# ESP32-WROOM-32.net
KiCad netlist of a schematic drawn in Altium Designer
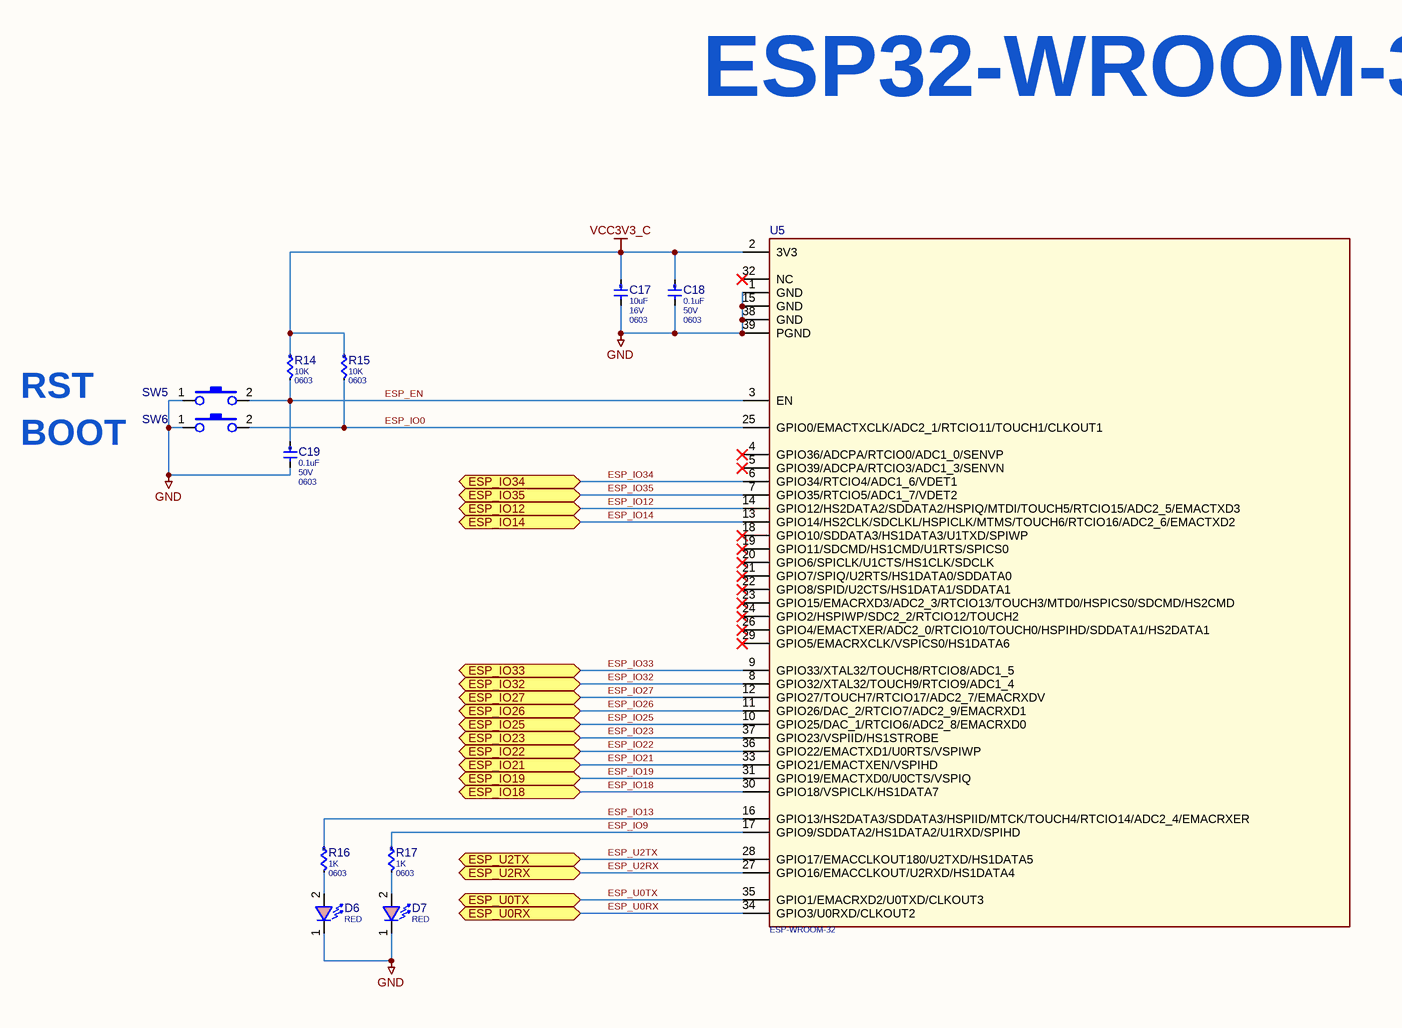
[diagram p0: ESP32-WROOM-32.SchDoc]

(export (version "E")
  (design (tool "Eeschema 10.0.6"))
  (components
    (comp (ref "C17")
      (value "10uF")
      (footprint "C0603")
      (description "CAP CER 10UF 10% 16V X5R 0603 SMD")
      (fields
        (field (name "TOLERANCE") "10%")
        (field (name "VOLTAGE") "16V")
        (field (name "PACK") "0603")
        (field (name "Comment") "10uF 16V 0603")
      )
      (libsource (lib "FENIKAA_LIB") (part "C0603_10uF_16V_10%"))
    )
    (comp (ref "C18")
      (value "0.1uF")
      (footprint "C0603")
      (description "CAP CER 0.1UF 10% 50V X7R 0603 SMD")
      (fields
        (field (name "TOLERANCE") "10%")
        (field (name "VOLTAGE") "50V")
        (field (name "PACK") "0603")
        (field (name "Comment") "0.1uF 50V 0603")
      )
      (libsource (lib "FENIKAA_LIB") (part "C0603_0.1uF_50V_10%"))
    )
    (comp (ref "C19")
      (value "0.1uF")
      (footprint "C0603")
      (description "CAP CER 0.1UF 10% 50V X7R 0603 SMD")
      (fields
        (field (name "TOLERANCE") "10%")
        (field (name "VOLTAGE") "50V")
        (field (name "PACK") "0603")
        (field (name "Comment") "0.1uF 50V 0603")
      )
      (libsource (lib "FENIKAA_LIB") (part "C0603_0.1uF_50V_10%"))
    )
    (comp (ref "D6")
      (value "LH R974-LP-1")
      (footprint "LED0805_RED")
      (description "LED IND RED 1.8V 20mA 0805 SMD")
      (fields (field (name "COLOR") "RED"))
      (libsource (lib "FENIKAA_LIB") (part "LED0805_RED"))
    )
    (comp (ref "D7")
      (value "LH R974-LP-1")
      (footprint "LED0805_RED")
      (description "LED IND RED 1.8V 20mA 0805 SMD")
      (fields (field (name "COLOR") "RED"))
      (libsource (lib "FENIKAA_LIB") (part "LED0805_RED"))
    )
    (comp (ref "R14")
      (value "10K")
      (footprint "R0603")
      (description "RES CHP 10K 1% 1/10W 0603 SMD")
      (fields (field (name "POWER") "1/10W") (field (name "PACK") "0603") (field (name "TOLERANCE") "1%"))
      (libsource (lib "FENIKAA_LIB") (part "R0603_10K_1/10W_1%"))
    )
    (comp (ref "R15")
      (value "10K")
      (footprint "R0603")
      (description "RES CHP 10K 1% 1/10W 0603 SMD")
      (fields (field (name "POWER") "1/10W") (field (name "PACK") "0603") (field (name "TOLERANCE") "1%"))
      (libsource (lib "FENIKAA_LIB") (part "R0603_10K_1/10W_1%"))
    )
    (comp (ref "R16")
      (value "1K")
      (footprint "R0603")
      (description "RES CHP 1K 1% 1/10W 0603 SMD")
      (fields (field (name "POWER") "1/10W") (field (name "PACK") "0603") (field (name "TOLERANCE") "1%"))
      (libsource (lib "FENIKAA_LIB") (part "R0603_1K_1/10W_1%"))
    )
    (comp (ref "R17")
      (value "1K")
      (footprint "R0603")
      (description "RES CHP 1K 1% 1/10W 0603 SMD")
      (fields (field (name "POWER") "1/10W") (field (name "PACK") "0603") (field (name "TOLERANCE") "1%"))
      (libsource (lib "FENIKAA_LIB") (part "R0603_1K_1/10W_1%"))
    )
    (comp (ref "SW5")
      (value "BTN 3x6x5 SMD")
      (footprint "BTN_6L3W5H")
      (description "SWT BTN 3x6x5 SMD")
      (libsource (lib "FENIKAA_LIB") (part "SWT_BTN_3x6x5"))
    )
    (comp (ref "SW6")
      (value "BTN 3x6x5 SMD")
      (footprint "BTN_6L3W5H")
      (description "SWT BTN 3x6x5 SMD")
      (libsource (lib "FENIKAA_LIB") (part "SWT_BTN_3x6x5"))
    )
    (comp (ref "U5")
      (value "ESP-WROOM-32")
      (footprint "ESP-WROOM-32")
      (description "MDL TRX ESP-WROOM-32  SMD")
      (fields (field (name "VOLTAGE") "3V ~ 3.6V") (field (name "MGR PN") "ESP-WROOM-32"))
      (libsource (lib "FENIKAA_LIB") (part "MDL_ESP-WROOM-32"))
    )
  )
  (nets
    (net (code "1") (name "/ESP_EN") (class "Default")
      (node (ref "C19") (pin "1") (pinfunction "1_1") (pintype "passive"))
      (node (ref "R14") (pin "2") (pinfunction "2_2") (pintype "passive"))
      (node (ref "SW5") (pin "2") (pinfunction "3,4_2") (pintype "passive"))
      (node (ref "U5") (pin "3") (pinfunction "EN_3") (pintype "passive"))
    )
    (net (code "2") (name "/ESP_IO0") (class "Default")
      (node (ref "R15") (pin "2") (pinfunction "2_2") (pintype "passive"))
      (node (ref "SW6") (pin "2") (pinfunction "3,4_2") (pintype "passive"))
      (node (ref "U5") (pin "25") (pinfunction "GPIO0/EMACTXCLK/ADC2_1/RTCIO11/TOUCH1/CLKOUT1_25") (pintype "passive"))
    )
    (net (code "3") (name "/ESP_IO9") (class "Default")
      (node (ref "R17") (pin "1") (pinfunction "1_1") (pintype "passive"))
      (node (ref "U5") (pin "17") (pinfunction "GPIO9/SDDATA2/HS1DATA2/U1RXD/SPIHD_17") (pintype "passive"))
    )
    (net (code "4") (name "/ESP_IO12") (class "Default")
      (node (ref "U5") (pin "14") (pinfunction "GPIO12/HS2DATA2/SDDATA2/HSPIQ/MTDI/TOUCH5/RTCIO15/ADC2_5/EMACTXD3_14") (pintype "passive"))
    )
    (net (code "5") (name "/ESP_IO13") (class "Default")
      (node (ref "R16") (pin "1") (pinfunction "1_1") (pintype "passive"))
      (node (ref "U5") (pin "16") (pinfunction "GPIO13/HS2DATA3/SDDATA3/HSPIID/MTCK/TOUCH4/RTCIO14/ADC2_4/EMACRXER_16") (pintype "passive"))
    )
    (net (code "6") (name "/ESP_IO14") (class "Default")
      (node (ref "U5") (pin "13") (pinfunction "GPIO14/HS2CLK/SDCLKL/HSPICLK/MTMS/TOUCH6/RTCIO16/ADC2_6/EMACTXD2_13") (pintype "passive"))
    )
    (net (code "7") (name "/ESP_IO18") (class "Default")
      (node (ref "U5") (pin "30") (pinfunction "GPIO18/VSPICLK/HS1DATA7_30") (pintype "passive"))
    )
    (net (code "8") (name "/ESP_IO19") (class "Default")
      (node (ref "U5") (pin "31") (pinfunction "GPIO19/EMACTXD0/U0CTS/VSPIQ_31") (pintype "passive"))
    )
    (net (code "9") (name "/ESP_IO21") (class "Default")
      (node (ref "U5") (pin "33") (pinfunction "GPIO21/EMACTXEN/VSPIHD_33") (pintype "passive"))
    )
    (net (code "10") (name "/ESP_IO22") (class "Default")
      (node (ref "U5") (pin "36") (pinfunction "GPIO22/EMACTXD1/U0RTS/VSPIWP_36") (pintype "passive"))
    )
    (net (code "11") (name "/ESP_IO23") (class "Default")
      (node (ref "U5") (pin "37") (pinfunction "GPIO23/VSPIID/HS1STROBE_37") (pintype "passive"))
    )
    (net (code "12") (name "/ESP_IO25") (class "Default")
      (node (ref "U5") (pin "10") (pinfunction "GPIO25/DAC_1/RTCIO6/ADC2_8/EMACRXD0_10") (pintype "passive"))
    )
    (net (code "13") (name "/ESP_IO26") (class "Default")
      (node (ref "U5") (pin "11") (pinfunction "GPIO26/DAC_2/RTCIO7/ADC2_9/EMACRXD1_11") (pintype "passive"))
    )
    (net (code "14") (name "/ESP_IO27") (class "Default")
      (node (ref "U5") (pin "12") (pinfunction "GPIO27/TOUCH7/RTCIO17/ADC2_7/EMACRXDV_12") (pintype "passive"))
    )
    (net (code "15") (name "/ESP_IO32") (class "Default")
      (node (ref "U5") (pin "8") (pinfunction "GPIO32/XTAL32/TOUCH9/RTCIO9/ADC1_4_8") (pintype "passive"))
    )
    (net (code "16") (name "/ESP_IO33") (class "Default")
      (node (ref "U5") (pin "9") (pinfunction "GPIO33/XTAL32/TOUCH8/RTCIO8/ADC1_5_9") (pintype "passive"))
    )
    (net (code "17") (name "/ESP_IO34") (class "Default")
      (node (ref "U5") (pin "6") (pinfunction "GPIO34/RTCIO4/ADC1_6/VDET1_6") (pintype "passive"))
    )
    (net (code "18") (name "/ESP_IO35") (class "Default")
      (node (ref "U5") (pin "7") (pinfunction "GPIO35/RTCIO5/ADC1_7/VDET2_7") (pintype "passive"))
    )
    (net (code "19") (name "/ESP_U0RX") (class "Default")
      (node (ref "U5") (pin "34") (pinfunction "GPIO3/U0RXD/CLKOUT2_34") (pintype "passive"))
    )
    (net (code "20") (name "/ESP_U0TX") (class "Default")
      (node (ref "U5") (pin "35") (pinfunction "GPIO1/EMACRXD2/U0TXD/CLKOUT3_35") (pintype "passive"))
    )
    (net (code "21") (name "/ESP_U2RX") (class "Default")
      (node (ref "U5") (pin "27") (pinfunction "GPIO16/EMACCLKOUT/U2RXD/HS1DATA4_27") (pintype "passive"))
    )
    (net (code "22") (name "/ESP_U2TX") (class "Default")
      (node (ref "U5") (pin "28") (pinfunction "GPIO17/EMACCLKOUT180/U2TXD/HS1DATA5_28") (pintype "passive"))
    )
    (net (code "23") (name "GND") (class "Default")
      (node (ref "C17") (pin "2") (pinfunction "2_2") (pintype "passive"))
      (node (ref "C18") (pin "2") (pinfunction "2_2") (pintype "passive"))
      (node (ref "C19") (pin "2") (pinfunction "2_2") (pintype "passive"))
      (node (ref "D6") (pin "1") (pinfunction "K_1") (pintype "passive"))
      (node (ref "D7") (pin "1") (pinfunction "K_1") (pintype "passive"))
      (node (ref "SW5") (pin "1") (pinfunction "1,2_1") (pintype "passive"))
      (node (ref "SW6") (pin "1") (pinfunction "1,2_1") (pintype "passive"))
      (node (ref "U5") (pin "1") (pinfunction "GND_1") (pintype "passive"))
      (node (ref "U5") (pin "15") (pinfunction "GND_15") (pintype "passive"))
      (node (ref "U5") (pin "38") (pinfunction "GND_38") (pintype "passive"))
      (node (ref "U5") (pin "39") (pinfunction "PGND_39") (pintype "passive"))
    )
    (net (code "24") (name "Net-(D6-A)") (class "Default")
      (node (ref "D6") (pin "2") (pinfunction "A_2") (pintype "passive"))
      (node (ref "R16") (pin "2") (pinfunction "2_2") (pintype "passive"))
    )
    (net (code "25") (name "Net-(D7-A)") (class "Default")
      (node (ref "D7") (pin "2") (pinfunction "A_2") (pintype "passive"))
      (node (ref "R17") (pin "2") (pinfunction "2_2") (pintype "passive"))
    )
    (net (code "26") (name "VCC3V3_C") (class "Default")
      (node (ref "C17") (pin "1") (pinfunction "1_1") (pintype "passive"))
      (node (ref "C18") (pin "1") (pinfunction "1_1") (pintype "passive"))
      (node (ref "R14") (pin "1") (pinfunction "1_1") (pintype "passive"))
      (node (ref "R15") (pin "1") (pinfunction "1_1") (pintype "passive"))
      (node (ref "U5") (pin "2") (pinfunction "3V3_2") (pintype "passive"))
    )
    (net (code "27") (name "unconnected-(U5-GPIO2{slash}HSPIWP{slash}SDC2_2{slash}RTCIO12{slash}TOUCH2-Pad24)") (class "Default")
      (node (ref "U5") (pin "24") (pinfunction "GPIO2/HSPIWP/SDC2_2/RTCIO12/TOUCH2_24") (pintype "passive+no_connect"))
    )
    (net (code "28") (name "unconnected-(U5-GPIO4{slash}EMACTXER{slash}ADC2_0{slash}RTCIO10{slash}TOUCH0{slash}HSPIHD{slash}SDDATA1{slash}HS2DATA1-Pad26)") (class "Default")
      (node (ref "U5") (pin "26") (pinfunction "GPIO4/EMACTXER/ADC2_0/RTCIO10/TOUCH0/HSPIHD/SDDATA1/HS2DATA1_26") (pintype "passive+no_connect"))
    )
    (net (code "29") (name "unconnected-(U5-GPIO5{slash}EMACRXCLK{slash}VSPICS0{slash}HS1DATA6-Pad29)") (class "Default")
      (node (ref "U5") (pin "29") (pinfunction "GPIO5/EMACRXCLK/VSPICS0/HS1DATA6_29") (pintype "passive+no_connect"))
    )
    (net (code "30") (name "unconnected-(U5-GPIO6{slash}SPICLK{slash}U1CTS{slash}HS1CLK{slash}SDCLK-Pad20)") (class "Default")
      (node (ref "U5") (pin "20") (pinfunction "GPIO6/SPICLK/U1CTS/HS1CLK/SDCLK_20") (pintype "passive+no_connect"))
    )
    (net (code "31") (name "unconnected-(U5-GPIO7{slash}SPIQ{slash}U2RTS{slash}HS1DATA0{slash}SDDATA0-Pad21)") (class "Default")
      (node (ref "U5") (pin "21") (pinfunction "GPIO7/SPIQ/U2RTS/HS1DATA0/SDDATA0_21") (pintype "passive+no_connect"))
    )
    (net (code "32") (name "unconnected-(U5-GPIO8{slash}SPID{slash}U2CTS{slash}HS1DATA1{slash}SDDATA1-Pad22)") (class "Default")
      (node (ref "U5") (pin "22") (pinfunction "GPIO8/SPID/U2CTS/HS1DATA1/SDDATA1_22") (pintype "passive+no_connect"))
    )
    (net (code "33") (name "unconnected-(U5-GPIO10{slash}SDDATA3{slash}HS1DATA3{slash}U1TXD{slash}SPIWP-Pad18)") (class "Default")
      (node (ref "U5") (pin "18") (pinfunction "GPIO10/SDDATA3/HS1DATA3/U1TXD/SPIWP_18") (pintype "passive+no_connect"))
    )
    (net (code "34") (name "unconnected-(U5-GPIO11{slash}SDCMD{slash}HS1CMD{slash}U1RTS{slash}SPICS0-Pad19)") (class "Default")
      (node (ref "U5") (pin "19") (pinfunction "GPIO11/SDCMD/HS1CMD/U1RTS/SPICS0_19") (pintype "passive+no_connect"))
    )
    (net (code "35") (name "unconnected-(U5-GPIO15{slash}EMACRXD3{slash}ADC2_3{slash}RTCIO13{slash}TOUCH3{slash}MTD0{slash}HSPICS0{slash}SDCMD{slash}HS2CMD-Pad23)") (class "Default")
      (node (ref "U5") (pin "23") (pinfunction "GPIO15/EMACRXD3/ADC2_3/RTCIO13/TOUCH3/MTD0/HSPICS0/SDCMD/HS2CMD_23") (pintype "passive+no_connect"))
    )
    (net (code "36") (name "unconnected-(U5-GPIO36{slash}ADCPA{slash}RTCIO0{slash}ADC1_0{slash}SENVP-Pad4)") (class "Default")
      (node (ref "U5") (pin "4") (pinfunction "GPIO36/ADCPA/RTCIO0/ADC1_0/SENVP_4") (pintype "passive+no_connect"))
    )
    (net (code "37") (name "unconnected-(U5-GPIO39{slash}ADCPA{slash}RTCIO3{slash}ADC1_3{slash}SENVN-Pad5)") (class "Default")
      (node (ref "U5") (pin "5") (pinfunction "GPIO39/ADCPA/RTCIO3/ADC1_3/SENVN_5") (pintype "passive+no_connect"))
    )
    (net (code "38") (name "unconnected-(U5-NC-Pad32)") (class "Default")
      (node (ref "U5") (pin "32") (pinfunction "NC_32") (pintype "passive+no_connect"))
    )
  )
)
